# TLV62569.net
KiCad netlist of a schematic drawn in Altium Designer
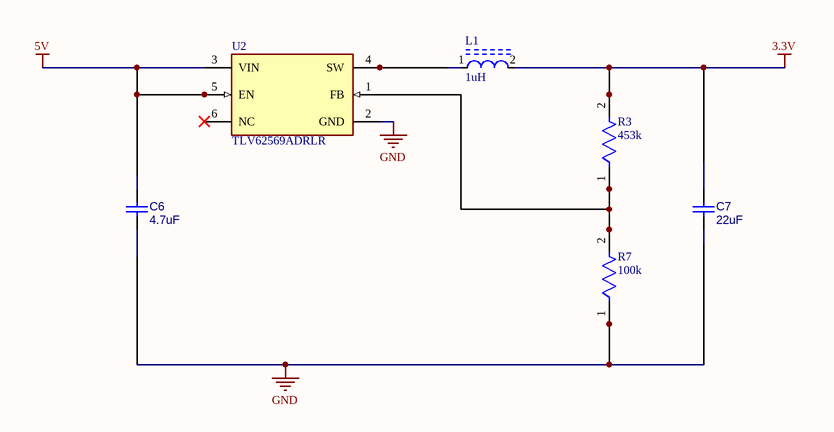
[diagram p0: TLV62569.SchDoc]

(export (version "E")
  (design (tool "Eeschema 10.0.6"))
  (components
    (comp (ref "C6")
      (value "4.7uF")
      (footprint "CAPC1608X09N")
      (description "CAP CER 4.7uF 25V X5R Symbols/Capacitor-Generic.SchLib")
      (fields (field (name "TOLERANCE") "10%") (field (name "VOLTAGE") "25V"))
      (libsource (lib "Satellite Team") (part "CAP-NP-1"))
    )
    (comp (ref "C7")
      (value "22uF")
      (footprint "CAPC1608X09N")
      (description "CAP CER 22uF 10V X5R Symbols/Capacitor-Generic.SchLib")
      (fields (field (name "VOLTAGE") "10V") (field (name "PART NUMBER") "CAP-0603-000010"))
      (libsource (lib "Satellite Team") (part "CAP-NP-1"))
    )
    (comp (ref "L1")
      (value "1uH")
      (footprint "FP-SRN8040-MFG")
      (description "FIXED IND 1UH 7.8A 10 MOHM SMD")
      (fields (field (name "TOLERANCE") "30%"))
      (libsource (lib "Altium Content Vault") (part "faee11374f111f4f771645e57fa9eac"))
    )
    (comp (ref "R3")
      (value "453k")
      (footprint "FP-CRCW0402-e3-MFG")
      (description "RES Thick Film, 453kΩ, 1%, 0.063W, 100ppm/°C, 0402")
      (fields (field (name "TOLERANCE") "1%"))
      (libsource (lib "Altium Content Vault") (part "1029c3af85768c4190bb7ad29bc67b5"))
    )
    (comp (ref "R7")
      (value "100k")
      (footprint "FP-CRCW0402-e3-IPC_C")
      (description "RES Thick Film, 100kΩ, 1%, 0.063W, 100ppm/°C, 0402")
      (fields (field (name "TOLERANCE") "1%"))
      (libsource (lib "Altium Content Vault") (part "1029c3af85768c4190bb7ad29bc67b5"))
    )
    (comp (ref "U2")
      (value "TLV62569ADRLR")
      (footprint "FP-DRL0006A-MFG")
      (description "IC REG BUCK ADJ 2A SOT563")
      (libsource (lib "Altium Content Vault") (part "c065b8f3016c1e0e14a773cb518fcf3"))
    )
  )
  (nets
    (net (code "1") (name "3.3V") (class "Default")
      (node (ref "C7") (pin "2") (pinfunction "2_2") (pintype "passive"))
      (node (ref "L1") (pin "2") (pinfunction "2_2") (pintype "passive"))
      (node (ref "R3") (pin "2") (pinfunction "2_2") (pintype "passive"))
    )
    (net (code "2") (name "5V") (class "Default")
      (node (ref "C6") (pin "2") (pinfunction "2_2") (pintype "passive"))
      (node (ref "U2") (pin "3") (pinfunction "VIN_3") (pintype "power_in"))
      (node (ref "U2") (pin "5") (pinfunction "EN_5") (pintype "input"))
    )
    (net (code "3") (name "GND") (class "Default")
      (node (ref "C6") (pin "1") (pinfunction "1_1") (pintype "passive"))
      (node (ref "C7") (pin "1") (pinfunction "1_1") (pintype "passive"))
      (node (ref "R7") (pin "1") (pinfunction "1_1") (pintype "passive"))
      (node (ref "U2") (pin "2") (pinfunction "GND_2") (pintype "power_in"))
    )
    (net (code "4") (name "Net-(U2-FB)") (class "Default")
      (node (ref "R3") (pin "1") (pinfunction "1_1") (pintype "passive"))
      (node (ref "R7") (pin "2") (pinfunction "2_2") (pintype "passive"))
      (node (ref "U2") (pin "1") (pinfunction "FB_1") (pintype "input"))
    )
    (net (code "5") (name "Net-(U2-SW)") (class "Default")
      (node (ref "L1") (pin "1") (pinfunction "1_1") (pintype "passive"))
      (node (ref "U2") (pin "4") (pinfunction "SW_4") (pintype "passive"))
    )
    (net (code "6") (name "unconnected-(U2-NC-Pad6)") (class "Default")
      (node (ref "U2") (pin "6") (pinfunction "NC_6") (pintype "passive+no_connect"))
    )
  )
)
